# E-19_WIFI_BT_802_15_4.net
KiCad netlist of a schematic drawn in Altium Designer
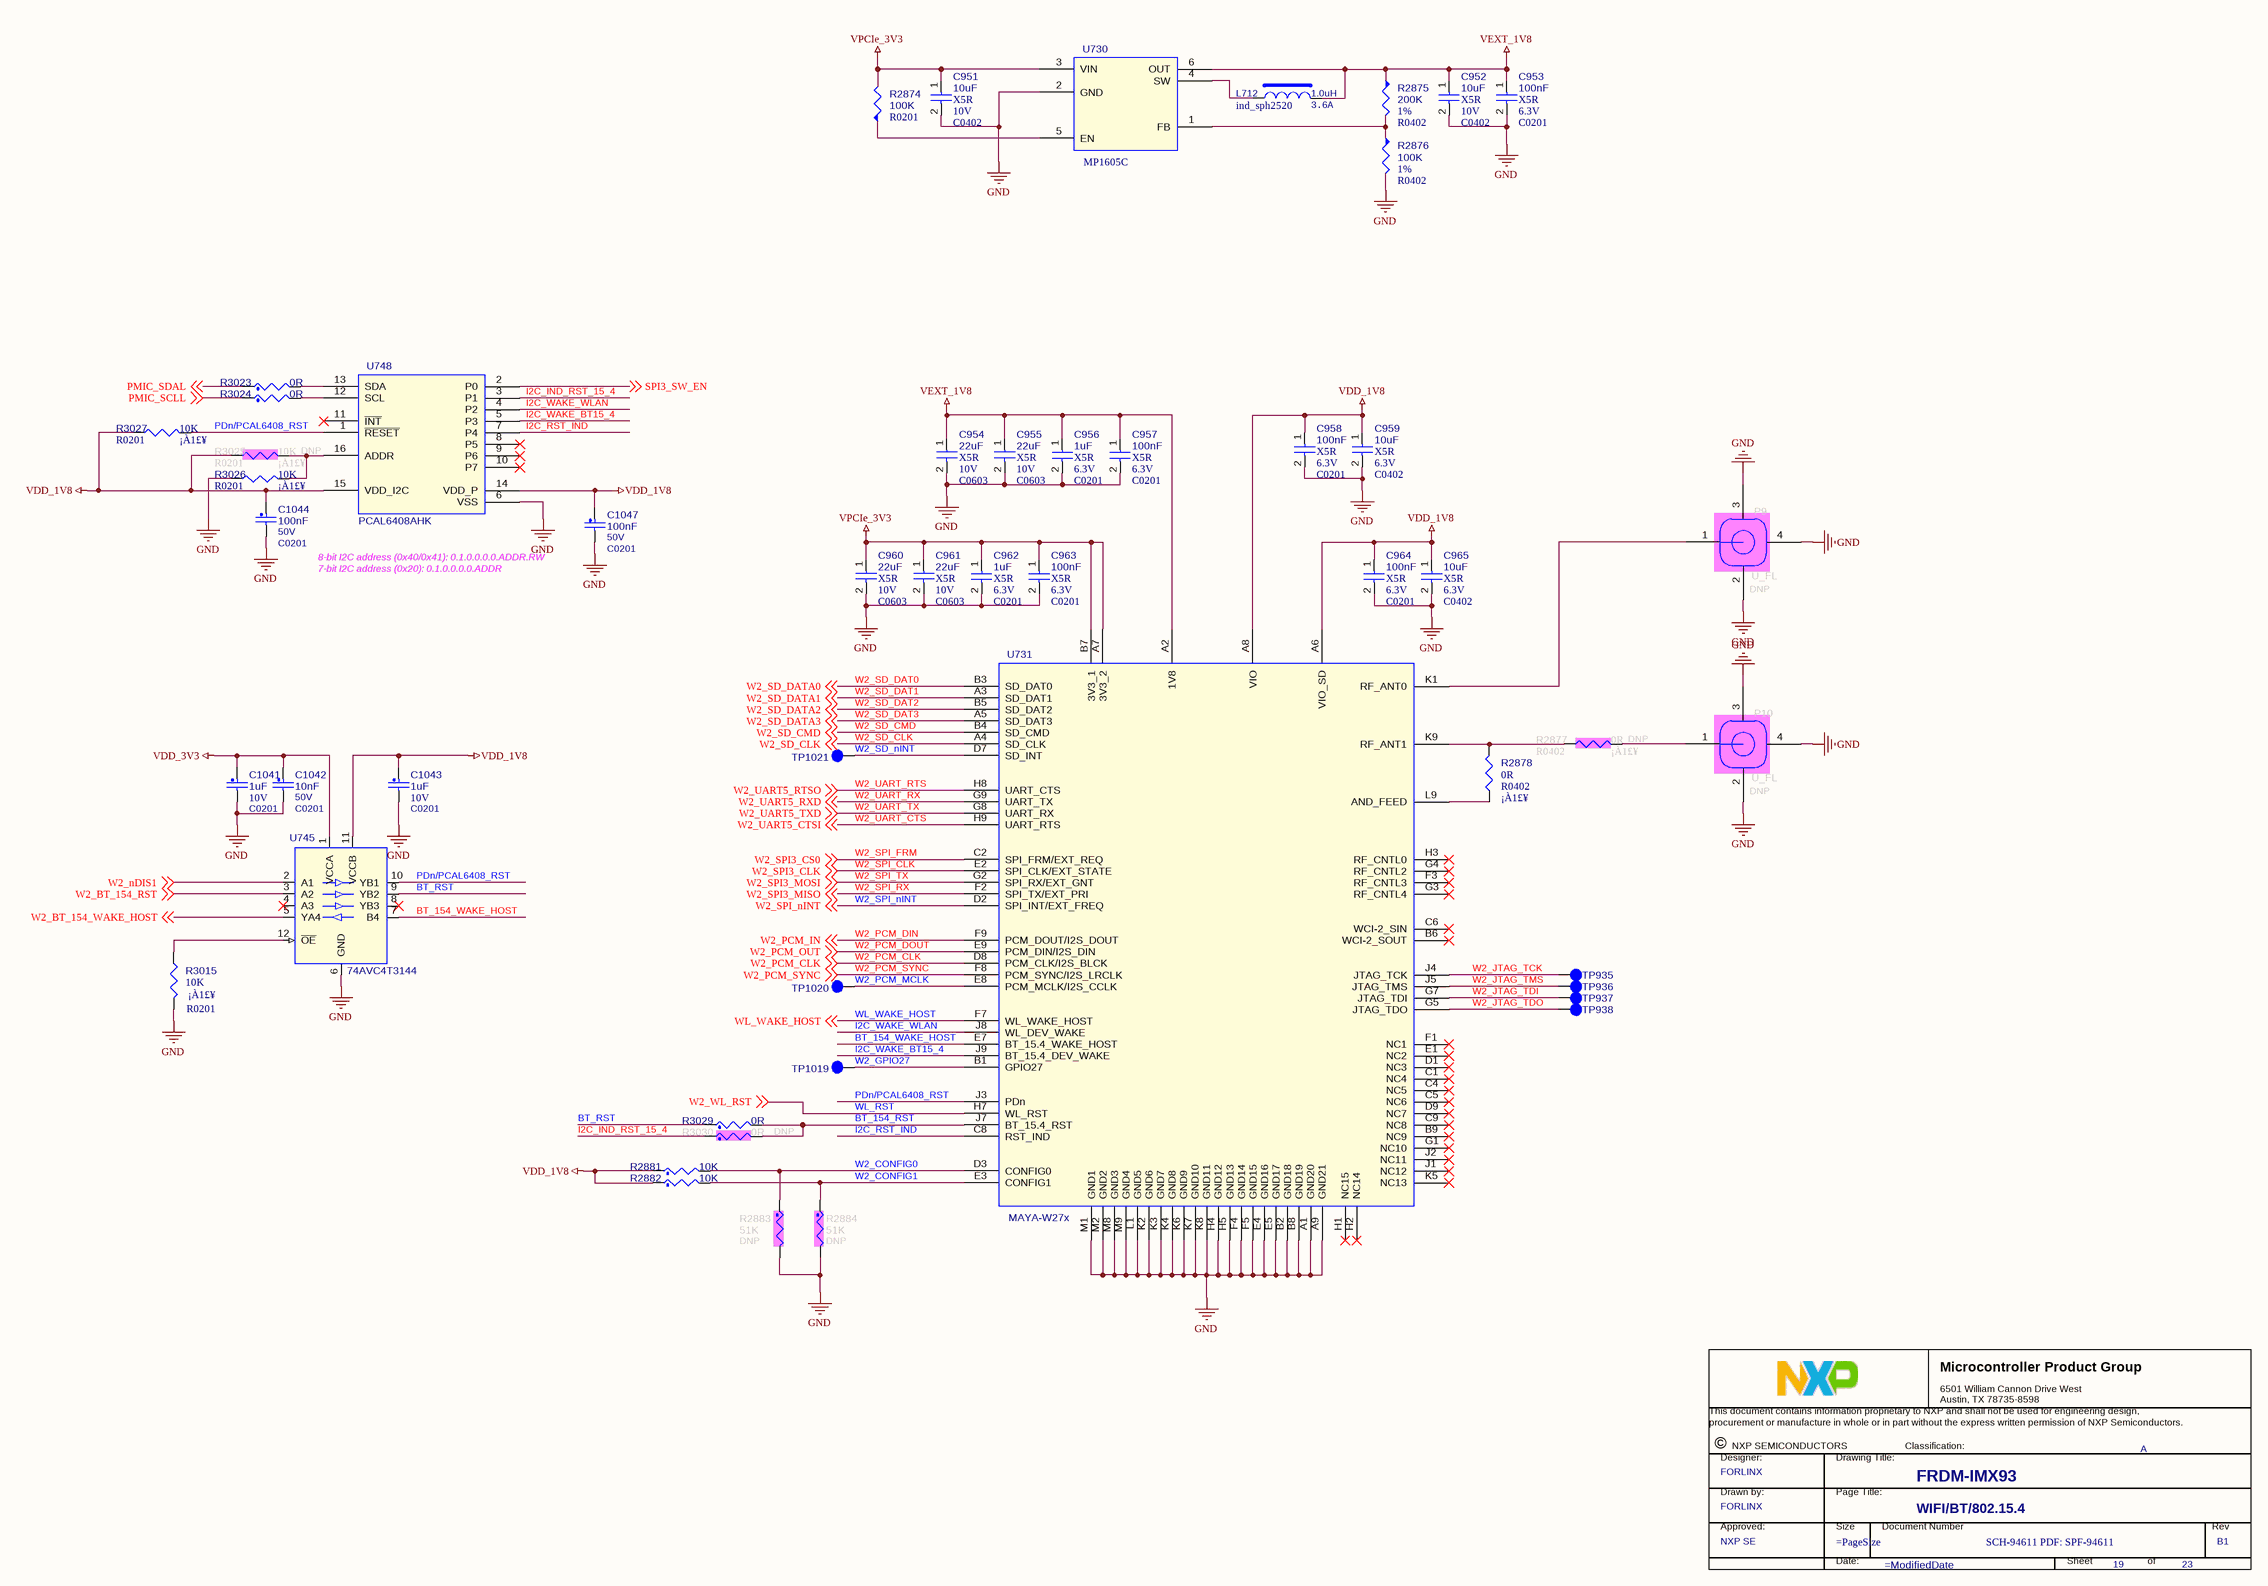
[diagram p0: E-19 WIFI_BT_802.15.4.SchDoc]

(export (version "E")
  (design (tool "Eeschema 10.0.6"))
  (components
    (comp (ref "C951")
      (value "10uF")
      (footprint "C0402")
      (description "0402,10uF,6.3V,+/-20%,X5R")
      (fields
        (field (name "VOLTAGE") "10V")
        (field (name "PCB FOOTPRINT") "C0402")
        (field (name "DIELECTRIC") "X5R")
        (field (name "MANUFACTURER") "murata")
        (field (name "TOLERANCE") "±20%")
        (field (name "CREATED BY") "JJJ")
      )
      (libsource (lib "*") (part "CAP NP"))
    )
    (comp (ref "C952")
      (value "10uF")
      (footprint "C0402")
      (description "0402,10uF,6.3V,+/-20%,X5R")
      (fields
        (field (name "VOLTAGE") "10V")
        (field (name "PCB FOOTPRINT") "C0402")
        (field (name "DIELECTRIC") "X5R")
        (field (name "MANUFACTURER") "murata")
        (field (name "TOLERANCE") "±20%")
        (field (name "CREATED BY") "JJJ")
      )
      (libsource (lib "*") (part "CAP NP"))
    )
    (comp (ref "C953")
      (value "100nF")
      (footprint "C0201")
      (description "0201,100nF,25V,+/-10%,X5R")
      (fields
        (field (name "VOLTAGE") "6.3V")
        (field (name "PCB FOOTPRINT") "C0201")
        (field (name "DIELECTRIC") "X5R")
        (field (name "TOLERANCE") "±10%")
        (field (name "MANUFACTURER") "FH(风华)")
        (field (name "CREATED BY") "JJJ")
      )
      (libsource (lib "*") (part "CAP NP"))
    )
    (comp (ref "C954")
      (value "22uF")
      (footprint "C0603")
      (description "0603,22uF,6.3V,+/-20%,X5R")
      (fields
        (field (name "VOLTAGE") "10V")
        (field (name "PCB FOOTPRINT") "C0603")
        (field (name "DIELECTRIC") "X5R")
        (field (name "MANUFACTURER") "TDK")
        (field (name "TOLERANCE") "10%")
        (field (name "CREATED BY") "JJJ")
      )
      (libsource (lib "*") (part "CAP NP"))
    )
    (comp (ref "C955")
      (value "22uF")
      (footprint "C0603")
      (description "0603,22uF,6.3V,+/-20%,X5R")
      (fields
        (field (name "VOLTAGE") "10V")
        (field (name "PCB FOOTPRINT") "C0603")
        (field (name "DIELECTRIC") "X5R")
        (field (name "MANUFACTURER") "TDK")
        (field (name "TOLERANCE") "10%")
        (field (name "CREATED BY") "JJJ")
      )
      (libsource (lib "*") (part "CAP NP"))
    )
    (comp (ref "C956")
      (value "1uF")
      (footprint "C0201")
      (description "0201,1uF,10V,+/-20%,X5R")
      (fields
        (field (name "VOLTAGE") "6.3V")
        (field (name "PCB FOOTPRINT") "C0201")
        (field (name "DIELECTRIC") "X5R")
        (field (name "MANUFACTURER") "FH(风华)")
        (field (name "TOLERANCE") "±10%")
        (field (name "CREATED BY") "JJJ")
      )
      (libsource (lib "*") (part "CAP NP"))
    )
    (comp (ref "C957")
      (value "100nF")
      (footprint "C0201")
      (description "0201,100nF,25V,+/-10%,X5R")
      (fields
        (field (name "VOLTAGE") "6.3V")
        (field (name "PCB FOOTPRINT") "C0201")
        (field (name "DIELECTRIC") "X5R")
        (field (name "TOLERANCE") "±10%")
        (field (name "MANUFACTURER") "FH(风华)")
        (field (name "CREATED BY") "JJJ")
      )
      (libsource (lib "*") (part "CAP NP"))
    )
    (comp (ref "C958")
      (value "100nF")
      (footprint "C0201")
      (description "0201,100nF,25V,+/-10%,X5R")
      (fields
        (field (name "VOLTAGE") "6.3V")
        (field (name "PCB FOOTPRINT") "C0201")
        (field (name "DIELECTRIC") "X5R")
        (field (name "MANUFACTURER") "FH(风华)")
        (field (name "TOLERANCE") "±10%")
        (field (name "CREATED BY") "JJJ")
      )
      (libsource (lib "*") (part "CAP NP"))
    )
    (comp (ref "C959")
      (value "10uF")
      (footprint "C0402")
      (description "0402,10uF,6.3V,+/-20%,X5R")
      (fields
        (field (name "VOLTAGE") "6.3V")
        (field (name "PCB FOOTPRINT") "C0402")
        (field (name "DIELECTRIC") "X5R")
        (field (name "MANUFACTURER") "FH(风华)")
        (field (name "TOLERANCE") "±10%")
        (field (name "CREATED BY") "JJJ")
      )
      (libsource (lib "*") (part "CAP NP"))
    )
    (comp (ref "C960")
      (value "22uF")
      (footprint "C0603")
      (description "0603,22uF,6.3V,+/-20%,X5R")
      (fields
        (field (name "VOLTAGE") "10V")
        (field (name "PCB FOOTPRINT") "C0603")
        (field (name "DIELECTRIC") "X5R")
        (field (name "MANUFACTURER") "TDK")
        (field (name "TOLERANCE") "10%")
        (field (name "CREATED BY") "JJJ")
      )
      (libsource (lib "*") (part "CAP NP"))
    )
    (comp (ref "C961")
      (value "22uF")
      (footprint "C0603")
      (description "0603,22uF,6.3V,+/-20%,X5R")
      (fields
        (field (name "VOLTAGE") "10V")
        (field (name "PCB FOOTPRINT") "C0603")
        (field (name "DIELECTRIC") "X5R")
        (field (name "MANUFACTURER") "TDK")
        (field (name "TOLERANCE") "10%")
        (field (name "CREATED BY") "JJJ")
      )
      (libsource (lib "*") (part "CAP NP"))
    )
    (comp (ref "C962")
      (value "1uF")
      (footprint "C0201")
      (description "0201,1uF,10V,+/-20%,X5R")
      (fields
        (field (name "VOLTAGE") "6.3V")
        (field (name "PCB FOOTPRINT") "C0201")
        (field (name "DIELECTRIC") "X5R")
        (field (name "TOLERANCE") "±10%")
        (field (name "MANUFACTURER") "FH(风华)")
        (field (name "CREATED BY") "JJJ")
      )
      (libsource (lib "*") (part "CAP NP"))
    )
    (comp (ref "C963")
      (value "100nF")
      (footprint "C0201")
      (description "0201,100nF,25V,+/-10%,X5R")
      (fields
        (field (name "VOLTAGE") "6.3V")
        (field (name "PCB FOOTPRINT") "C0201")
        (field (name "DIELECTRIC") "X5R")
        (field (name "TOLERANCE") "±10%")
        (field (name "MANUFACTURER") "FH(风华)")
        (field (name "CREATED BY") "JJJ")
      )
      (libsource (lib "*") (part "CAP NP"))
    )
    (comp (ref "C964")
      (value "100nF")
      (footprint "C0201")
      (description "0201,100nF,25V,+/-10%,X5R")
      (fields
        (field (name "VOLTAGE") "6.3V")
        (field (name "PCB FOOTPRINT") "C0201")
        (field (name "DIELECTRIC") "X5R")
        (field (name "MANUFACTURER") "FH(风华)")
        (field (name "TOLERANCE") "±10%")
        (field (name "CREATED BY") "JJJ")
      )
      (libsource (lib "*") (part "CAP NP"))
    )
    (comp (ref "C965")
      (value "10uF")
      (footprint "C0402")
      (description "0402,10uF,6.3V,+/-20%,X5R")
      (fields
        (field (name "VOLTAGE") "6.3V")
        (field (name "PCB FOOTPRINT") "C0402")
        (field (name "DIELECTRIC") "X5R")
        (field (name "MANUFACTURER") "FH(风华)")
        (field (name "TOLERANCE") "±10%")
        (field (name "CREATED BY") "JJJ")
      )
      (libsource (lib "*") (part "CAP NP"))
    )
    (comp (ref "C1041")
      (value "1uF")
      (footprint "C0201")
      (description "0201,1uF,10V,+/-20%,X5R")
      (fields
        (field (name "PCB FOOTPRINT") "C0201")
        (field (name "VOLTAGE") "10V")
        (field (name "TOLERANCE") "10%")
      )
      (libsource (lib "*") (part "CAP_NP"))
    )
    (comp (ref "C1042")
      (value "10nF")
      (footprint "C0201")
      (description "0201,10nF,25V,+/-10%,X7R")
      (fields
        (field (name "PCB FOOTPRINT") "C0201")
        (field (name "VOLTAGE") "50V")
        (field (name "TOLERANCE") "10%")
      )
      (libsource (lib "*") (part "CAP_NP"))
    )
    (comp (ref "C1043")
      (value "1uF")
      (footprint "C0201")
      (description "0201,1uF,10V,+/-20%,X5R")
      (fields
        (field (name "PCB FOOTPRINT") "C0201")
        (field (name "VOLTAGE") "10V")
        (field (name "TOLERANCE") "10%")
      )
      (libsource (lib "*") (part "CAP_NP"))
    )
    (comp (ref "C1044")
      (value "100nF")
      (footprint "C0201")
      (description "0201,100nF,25V,+/-10%,X5R")
      (fields
        (field (name "PCB FOOTPRINT") "C0201")
        (field (name "TOLERANCE") "10%")
        (field (name "VOLTAGE") "50V")
      )
      (libsource (lib "*") (part "CAP_NP"))
    )
    (comp (ref "C1047")
      (value "100nF")
      (footprint "C0201")
      (description "0201,100nF,25V,+/-10%,X5R")
      (fields
        (field (name "PCB FOOTPRINT") "C0201")
        (field (name "VOLTAGE") "50V")
        (field (name "TOLERANCE") "10%")
      )
      (libsource (lib "*") (part "CAP_NP"))
    )
    (comp (ref "L712")
      (value "1.0uH")
      (footprint "ind_sph2520")
      (description "1uH ,2.5*2.0*1.2mm, 3.6A")
      (fields
        (field (name "ISAT") "3.6A")
        (field (name "PCB FOOTPRINT") "ind_sph2520")
        (field (name "TOLERANCE") "20%")
        (field (name "MANUFACTURER") "TDK")
        (field (name "CREATED BY") "JJJ")
      )
      (libsource (lib "*") (part "INDUCTORS OF FERRITE"))
    )
    (comp (ref "P9")
      (value "U_FL")
      (footprint "IPEX_4")
      (description "IPEX transposon, 4th generation")
      (fields (field (name "ASSY_OPT") "DNP"))
      (libsource (lib "*") (part "U_FL"))
    )
    (comp (ref "P10")
      (value "U_FL")
      (footprint "IPEX_4")
      (description "IPEX transposon, 4th generation")
      (fields (field (name "ASSY_OPT") "DNP"))
      (libsource (lib "*") (part "U_FL"))
    )
    (comp (ref "R2874")
      (value "100K")
      (footprint "R0201")
      (description "0201,100K,+/-1%")
      (fields
        (field (name "TOLERANCE") "5%")
        (field (name "PCB FOOTPRINT") "R0201")
        (field (name "MANUFACTURER") "YAGEO")
        (field (name "CREATED BY") "YTL")
      )
      (libsource (lib "*") (part "RESISTOR5"))
    )
    (comp (ref "R2875")
      (value "200K")
      (footprint "R0402")
      (description "0402,200K,+/-1%")
      (fields
        (field (name "PCB FOOTPRINT") "R0402")
        (field (name "TOLERANCE") "1%")
        (field (name "MANUFACTURER") "YAGEO")
        (field (name "CREATED BY") "YTL")
      )
      (libsource (lib "*") (part "RESISTOR1"))
    )
    (comp (ref "R2876")
      (value "100K")
      (footprint "R0402")
      (description "0402,100K,+/-1%")
      (fields
        (field (name "PCB FOOTPRINT") "R0402")
        (field (name "TOLERANCE") "1%")
        (field (name "MANUFACTURER") "YAGEO")
        (field (name "CREATED BY") "YTL")
      )
      (libsource (lib "*") (part "RESISTOR1"))
    )
    (comp (ref "R2877")
      (value "0R")
      (footprint "R0402")
      (description "0402,0Ohm,+/-1%")
      (fields
        (field (name "PCB FOOTPRINT") "R0402")
        (field (name "PRECISION") "±1％")
        (field (name "ASSY_OPT") "DNP")
      )
      (libsource (lib "*") (part "R0402,4.7K"))
    )
    (comp (ref "R2878")
      (value "0R")
      (footprint "R0402")
      (description "0402,0Ohm,+/-1%")
      (fields (field (name "PCB FOOTPRINT") "R0402") (field (name "PRECISION") "±1％"))
      (libsource (lib "*") (part "R0402,4.7K"))
    )
    (comp (ref "R2881")
      (value "10K")
      (footprint "R0201")
      (description "0201,10K,+/-5%")
      (fields (field (name "TOLERANCE") "5%") (field (name "VOLTAGE") "1/16W"))
      (libsource (lib "*") (part "RES"))
    )
    (comp (ref "R2882")
      (value "10K")
      (footprint "R0201")
      (description "0201,10K,+/-5%")
      (fields (field (name "TOLERANCE") "5%") (field (name "VOLTAGE") "1/16W"))
      (libsource (lib "*") (part "RES"))
    )
    (comp (ref "R2883")
      (value "51K")
      (footprint "R0201")
      (description "0201,51K,+/-1%,RC-01W5102FT")
      (fields
        (field (name "ASSY_OPT") "DNP")
        (field (name "TOLERANCE") "5%")
        (field (name "VOLTAGE") "1/16W")
      )
      (libsource (lib "*") (part "RES"))
    )
    (comp (ref "R2884")
      (value "51K")
      (footprint "R0201")
      (description "0201,51K,+/-1%,RC-01W5102FT")
      (fields
        (field (name "ASSY_OPT") "DNP")
        (field (name "VOLTAGE") "1/16W")
        (field (name "TOLERANCE") "5%")
      )
      (libsource (lib "*") (part "RES"))
    )
    (comp (ref "R3015")
      (value "10K")
      (footprint "R0201")
      (description "0201,10K,+/-5%")
      (fields (field (name "PRECISION") "±1％") (field (name "PCB FOOTPRINT") "R0201"))
      (libsource (lib "*") (part "R0402,10K"))
    )
    (comp (ref "R3023")
      (value "0R")
      (footprint "R0201")
      (description "0201,0Ohm,+/-5%")
      (fields (field (name "TOLERANCE") "5%") (field (name "VOLTAGE") "1/16W"))
      (libsource (lib "*") (part "RES"))
    )
    (comp (ref "R3024")
      (value "0R")
      (footprint "R0201")
      (description "0201,0Ohm,+/-5%")
      (fields (field (name "TOLERANCE") "5%") (field (name "VOLTAGE") "1/16W"))
      (libsource (lib "*") (part "RES"))
    )
    (comp (ref "R3025")
      (value "10K")
      (footprint "R0201")
      (description "0201,10K,+/-5%")
      (fields
        (field (name "PRECISION") "±1％")
        (field (name "PCB FOOTPRINT") "R0201")
        (field (name "ASSY_OPT") "DNP")
      )
      (libsource (lib "*") (part "R0402,10K"))
    )
    (comp (ref "R3026")
      (value "10K")
      (footprint "R0201")
      (description "0201,10K,+/-5%")
      (fields (field (name "PRECISION") "±1％") (field (name "PCB FOOTPRINT") "R0201"))
      (libsource (lib "*") (part "R0402,10K"))
    )
    (comp (ref "R3027")
      (value "10K")
      (footprint "R0201")
      (description "0201,10K,+/-5%")
      (fields (field (name "PRECISION") "±1％") (field (name "PCB FOOTPRINT") "R0201"))
      (libsource (lib "*") (part "R0402,10K"))
    )
    (comp (ref "R3029")
      (value "0R")
      (footprint "R0201")
      (description "0201,0Ohm,+/-5%")
      (fields (field (name "TOLERANCE") "5%") (field (name "VOLTAGE") "1/16W"))
      (libsource (lib "*") (part "RES"))
    )
    (comp (ref "R3030")
      (value "0R")
      (footprint "R0201")
      (description "0201,0Ohm,+/-5%")
      (fields
        (field (name "ASSY_OPT") "DNP")
        (field (name "TOLERANCE") "5%")
        (field (name "VOLTAGE") "1/16W")
      )
      (libsource (lib "*") (part "RES"))
    )
    (comp (ref "TP935")
      (value "TPAD_015")
      (footprint "tpad_015")
      (description "no part to order")
      (libsource (lib "*") (part "TESTLOOP"))
    )
    (comp (ref "TP936")
      (value "TPAD_015")
      (footprint "tpad_015")
      (description "no part to order")
      (libsource (lib "*") (part "TESTLOOP"))
    )
    (comp (ref "TP937")
      (value "TPAD_015")
      (footprint "tpad_015")
      (description "no part to order")
      (libsource (lib "*") (part "TESTLOOP"))
    )
    (comp (ref "TP938")
      (value "TPAD_015")
      (footprint "tpad_015")
      (description "no part to order")
      (libsource (lib "*") (part "TESTLOOP"))
    )
    (comp (ref "TP1019")
      (value "TPAD_015")
      (footprint "tpad_015")
      (description "no part to order")
      (libsource (lib "*") (part "TESTLOOP"))
    )
    (comp (ref "TP1020")
      (value "TPAD_015")
      (footprint "tpad_015")
      (description "no part to order")
      (libsource (lib "*") (part "TESTLOOP"))
    )
    (comp (ref "TP1021")
      (value "TPAD_015")
      (footprint "tpad_015")
      (description "no part to order")
      (libsource (lib "*") (part "TESTLOOP"))
    )
    (comp (ref "U730")
      (value "MP1605C")
      (footprint "SOT563")
      (description "MP1605GTF,SOT563")
      (libsource (lib "*") (part "MP1605C"))
    )
    (comp (ref "U731")
      (value "MAYA-W27x")
      (footprint "MAYA-W2")
      (description "MAYA-W276,LGA86,10.4*14.3*2.0mm,0-70+C(SDIO,UART,SPI)")
      (libsource (lib "*") (part "MAYA-W27x"))
    )
    (comp (ref "U745")
      (value "74AVC4T3144")
      (footprint "uqfn12_1p7x2mm")
      (description "74AVC4T3144GU12,XQFN12,1.70*2.0,4-bit dual-supply buffer/level translator;3-state")
      (fields (field (name "VOLTAGE") "0.9-3.6V"))
      (libsource (lib "*") (part "TXB0304RUT_12P_B_0"))
    )
    (comp (ref "U748")
      (value "PCAL6408AHK")
      (footprint "XQFN16")
      (description "PCAL6408AHK,XQFN16,-40~85+C,I2C Extended 8-bit GPIO")
      (libsource (lib "*") (part "PCAL6408AHK"))
    )
  )
  (nets
    (net (code "1") (name "/BT_154_RST") (class "Default")
      (node (ref "R3029") (pin "2") (pinfunction "2_2") (pintype "passive"))
      (node (ref "R3030") (pin "2") (pinfunction "2_2") (pintype "passive"))
      (node (ref "U731") (pin "J7") (pinfunction "BT_15.4_RST_J7") (pintype "passive"))
    )
    (net (code "2") (name "/BT_154_WAKE_HOST") (class "Default")
      (node (ref "U731") (pin "E7") (pinfunction "BT_15.4_WAKE_HOST_E7") (pintype "passive"))
      (node (ref "U745") (pin "7") (pinfunction "B4_7") (pintype "bidirectional"))
    )
    (net (code "3") (name "/BT_RST") (class "Default")
      (node (ref "R3029") (pin "1") (pinfunction "1_1") (pintype "passive"))
      (node (ref "U745") (pin "9") (pinfunction "YB2_9") (pintype "bidirectional"))
    )
    (net (code "4") (name "/I2C_IND_RST_15_4") (class "Default")
      (node (ref "R3030") (pin "1") (pinfunction "1_1") (pintype "passive"))
      (node (ref "U748") (pin "3") (pinfunction "P1_3") (pintype "passive"))
    )
    (net (code "5") (name "/I2C_RST_IND") (class "Default")
      (node (ref "U731") (pin "C8") (pinfunction "RST_IND_C8") (pintype "passive"))
      (node (ref "U748") (pin "7") (pinfunction "P4_7") (pintype "passive"))
    )
    (net (code "6") (name "/I2C_WAKE_BT15_4") (class "Default")
      (node (ref "U731") (pin "J9") (pinfunction "BT_15.4_DEV_WAKE_J9") (pintype "passive"))
      (node (ref "U748") (pin "5") (pinfunction "P3_5") (pintype "passive"))
    )
    (net (code "7") (name "/I2C_WAKE_WLAN") (class "Default")
      (node (ref "U731") (pin "J8") (pinfunction "WL_DEV_WAKE_J8") (pintype "passive"))
      (node (ref "U748") (pin "4") (pinfunction "P2_4") (pintype "passive"))
    )
    (net (code "8") (name "/PDn{slash}PCAL6408_RST") (class "Default")
      (node (ref "R3027") (pin "2") (pinfunction "2_2") (pintype "passive"))
      (node (ref "U731") (pin "J3") (pinfunction "PDn_J3") (pintype "passive"))
      (node (ref "U745") (pin "10") (pinfunction "YB1_10") (pintype "bidirectional"))
      (node (ref "U748") (pin "1") (pinfunction "~{RESET}_1") (pintype "passive"))
    )
    (net (code "9") (name "/W2_CONFIG0") (class "Default")
      (node (ref "R2881") (pin "2") (pinfunction "2_2") (pintype "passive"))
      (node (ref "R2883") (pin "1") (pinfunction "1_1") (pintype "passive"))
      (node (ref "U731") (pin "D3") (pinfunction "CONFIG0_D3") (pintype "passive"))
    )
    (net (code "10") (name "/W2_CONFIG1") (class "Default")
      (node (ref "R2882") (pin "2") (pinfunction "2_2") (pintype "passive"))
      (node (ref "R2884") (pin "1") (pinfunction "1_1") (pintype "passive"))
      (node (ref "U731") (pin "E3") (pinfunction "CONFIG1_E3") (pintype "passive"))
    )
    (net (code "11") (name "/W2_GPIO27") (class "Default")
      (node (ref "TP1019") (pin "1") (pinfunction "Pin1_1") (pintype "passive"))
      (node (ref "U731") (pin "B1") (pinfunction "GPIO27_B1") (pintype "passive"))
    )
    (net (code "12") (name "/W2_JTAG_TCK") (class "Default")
      (node (ref "TP935") (pin "1") (pinfunction "Pin1_1") (pintype "passive"))
      (node (ref "U731") (pin "J4") (pinfunction "JTAG_TCK_J4") (pintype "passive"))
    )
    (net (code "13") (name "/W2_JTAG_TDI") (class "Default")
      (node (ref "TP937") (pin "1") (pinfunction "Pin1_1") (pintype "passive"))
      (node (ref "U731") (pin "G7") (pinfunction "JTAG_TDI_G7") (pintype "passive"))
    )
    (net (code "14") (name "/W2_JTAG_TDO") (class "Default")
      (node (ref "TP938") (pin "1") (pinfunction "Pin1_1") (pintype "passive"))
      (node (ref "U731") (pin "G5") (pinfunction "JTAG_TDO_G5") (pintype "passive"))
    )
    (net (code "15") (name "/W2_JTAG_TMS") (class "Default")
      (node (ref "TP936") (pin "1") (pinfunction "Pin1_1") (pintype "passive"))
      (node (ref "U731") (pin "J5") (pinfunction "JTAG_TMS_J5") (pintype "passive"))
    )
    (net (code "16") (name "/W2_PCM_MCLK") (class "Default")
      (node (ref "TP1020") (pin "1") (pinfunction "Pin1_1") (pintype "passive"))
      (node (ref "U731") (pin "E8") (pinfunction "PCM_MCLK/I2S_CCLK_E8") (pintype "passive"))
    )
    (net (code "17") (name "/W2_SD_nINT") (class "Default")
      (node (ref "TP1021") (pin "1") (pinfunction "Pin1_1") (pintype "passive"))
      (node (ref "U731") (pin "D7") (pinfunction "SD_INT_D7") (pintype "passive"))
    )
    (net (code "18") (name "GND") (class "Default")
      (node (ref "C1041") (pin "2") (pinfunction "2_2") (pintype "passive"))
      (node (ref "C1042") (pin "2") (pinfunction "2_2") (pintype "passive"))
      (node (ref "C1043") (pin "2") (pinfunction "2_2") (pintype "passive"))
      (node (ref "C1044") (pin "2") (pinfunction "2_2") (pintype "passive"))
      (node (ref "C1047") (pin "2") (pinfunction "2_2") (pintype "passive"))
      (node (ref "C951") (pin "2") (pinfunction "2_2") (pintype "passive"))
      (node (ref "C952") (pin "2") (pinfunction "2_2") (pintype "passive"))
      (node (ref "C953") (pin "2") (pinfunction "2_2") (pintype "passive"))
      (node (ref "C954") (pin "2") (pinfunction "2_2") (pintype "passive"))
      (node (ref "C955") (pin "2") (pinfunction "2_2") (pintype "passive"))
      (node (ref "C956") (pin "2") (pinfunction "2_2") (pintype "passive"))
      (node (ref "C957") (pin "2") (pinfunction "2_2") (pintype "passive"))
      (node (ref "C958") (pin "2") (pinfunction "2_2") (pintype "passive"))
      (node (ref "C959") (pin "2") (pinfunction "2_2") (pintype "passive"))
      (node (ref "C960") (pin "2") (pinfunction "2_2") (pintype "passive"))
      (node (ref "C961") (pin "2") (pinfunction "2_2") (pintype "passive"))
      (node (ref "C962") (pin "2") (pinfunction "2_2") (pintype "passive"))
      (node (ref "C963") (pin "2") (pinfunction "2_2") (pintype "passive"))
      (node (ref "C964") (pin "2") (pinfunction "2_2") (pintype "passive"))
      (node (ref "C965") (pin "2") (pinfunction "2_2") (pintype "passive"))
      (node (ref "P10") (pin "2") (pinfunction "2_2") (pintype "passive"))
      (node (ref "P10") (pin "3") (pinfunction "3_3") (pintype "passive"))
      (node (ref "P10") (pin "4") (pinfunction "4_4") (pintype "passive"))
      (node (ref "P9") (pin "2") (pinfunction "2_2") (pintype "passive"))
      (node (ref "P9") (pin "3") (pinfunction "3_3") (pintype "passive"))
      (node (ref "P9") (pin "4") (pinfunction "4_4") (pintype "passive"))
      (node (ref "R2876") (pin "2") (pinfunction "2_2") (pintype "passive"))
      (node (ref "R2883") (pin "2") (pinfunction "2_2") (pintype "passive"))
      (node (ref "R2884") (pin "2") (pinfunction "2_2") (pintype "passive"))
      (node (ref "R3015") (pin "2") (pinfunction "2_2") (pintype "passive"))
      (node (ref "R3026") (pin "1") (pinfunction "1_1") (pintype "passive"))
      (node (ref "U730") (pin "2") (pinfunction "GND_2") (pintype "passive"))
      (node (ref "U731") (pin "A1") (pinfunction "GND20_A1") (pintype "passive"))
      (node (ref "U731") (pin "A9") (pinfunction "GND21_A9") (pintype "passive"))
      (node (ref "U731") (pin "B2") (pinfunction "GND18_B2") (pintype "passive"))
      (node (ref "U731") (pin "B8") (pinfunction "GND19_B8") (pintype "passive"))
      (node (ref "U731") (pin "E4") (pinfunction "GND16_E4") (pintype "passive"))
      (node (ref "U731") (pin "E5") (pinfunction "GND17_E5") (pintype "passive"))
      (node (ref "U731") (pin "F4") (pinfunction "GND14_F4") (pintype "passive"))
      (node (ref "U731") (pin "F5") (pinfunction "GND15_F5") (pintype "passive"))
      (node (ref "U731") (pin "H4") (pinfunction "GND12_H4") (pintype "passive"))
      (node (ref "U731") (pin "H5") (pinfunction "GND13_H5") (pintype "passive"))
      (node (ref "U731") (pin "K2") (pinfunction "GND6_K2") (pintype "passive"))
      (node (ref "U731") (pin "K3") (pinfunction "GND7_K3") (pintype "passive"))
      (node (ref "U731") (pin "K4") (pinfunction "GND8_K4") (pintype "passive"))
      (node (ref "U731") (pin "K6") (pinfunction "GND9_K6") (pintype "passive"))
      (node (ref "U731") (pin "K7") (pinfunction "GND10_K7") (pintype "passive"))
      (node (ref "U731") (pin "K8") (pinfunction "GND11_K8") (pintype "passive"))
      (node (ref "U731") (pin "L1") (pinfunction "GND5_L1") (pintype "passive"))
      (node (ref "U731") (pin "M1") (pinfunction "GND1_M1") (pintype "passive"))
      (node (ref "U731") (pin "M2") (pinfunction "GND2_M2") (pintype "passive"))
      (node (ref "U731") (pin "M8") (pinfunction "GND3_M8") (pintype "passive"))
      (node (ref "U731") (pin "M9") (pinfunction "GND4_M9") (pintype "passive"))
      (node (ref "U745") (pin "6") (pinfunction "GND_6") (pintype "power_in"))
      (node (ref "U748") (pin "6") (pinfunction "VSS_6") (pintype "passive"))
    )
    (net (code "19") (name "Net-(P10-Pad1)") (class "Default")
      (node (ref "P10") (pin "1") (pinfunction "1_1") (pintype "passive"))
      (node (ref "R2877") (pin "2") (pinfunction "2_2") (pintype "passive"))
    )
    (net (code "20") (name "Net-(U730-EN)") (class "Default")
      (node (ref "R2874") (pin "1") (pinfunction "1_1") (pintype "passive"))
      (node (ref "U730") (pin "5") (pinfunction "EN_5") (pintype "passive"))
    )
    (net (code "21") (name "Net-(U730-FB)") (class "Default")
      (node (ref "R2875") (pin "2") (pinfunction "2_2") (pintype "passive"))
      (node (ref "R2876") (pin "1") (pinfunction "1_1") (pintype "passive"))
      (node (ref "U730") (pin "1") (pinfunction "FB_1") (pintype "passive"))
    )
    (net (code "22") (name "Net-(U730-SW)") (class "Default")
      (node (ref "L712") (pin "1") (pinfunction "1_1") (pintype "passive"))
      (node (ref "U730") (pin "4") (pinfunction "SW_4") (pintype "passive"))
    )
    (net (code "23") (name "Net-(U731-AND_FEED)") (class "Default")
      (node (ref "R2878") (pin "1") (pinfunction "1_1") (pintype "passive"))
      (node (ref "U731") (pin "L9") (pinfunction "AND_FEED_L9") (pintype "passive"))
    )
    (net (code "24") (name "Net-(U731-RF_ANT0)") (class "Default")
      (node (ref "P9") (pin "1") (pinfunction "1_1") (pintype "passive"))
      (node (ref "U731") (pin "K1") (pinfunction "RF_ANT0_K1") (pintype "passive"))
    )
    (net (code "25") (name "Net-(U731-RF_ANT1)") (class "Default")
      (node (ref "R2877") (pin "1") (pinfunction "1_1") (pintype "passive"))
      (node (ref "R2878") (pin "2") (pinfunction "2_2") (pintype "passive"))
      (node (ref "U731") (pin "K9") (pinfunction "RF_ANT1_K9") (pintype "passive"))
    )
    (net (code "26") (name "Net-(U745-~{OE})") (class "Default")
      (node (ref "R3015") (pin "1") (pinfunction "1_1") (pintype "passive"))
      (node (ref "U745") (pin "12") (pinfunction "~{OE}_12") (pintype "input"))
    )
    (net (code "27") (name "Net-(U748-ADDR)") (class "Default")
      (node (ref "R3025") (pin "2") (pinfunction "2_2") (pintype "passive"))
      (node (ref "R3026") (pin "2") (pinfunction "2_2") (pintype "passive"))
      (node (ref "U748") (pin "16") (pinfunction "ADDR_16") (pintype "passive"))
    )
    (net (code "28") (name "Net-(U748-SCL)") (class "Default")
      (node (ref "R3024") (pin "2") (pinfunction "2_2") (pintype "passive"))
      (node (ref "U748") (pin "12") (pinfunction "SCL_12") (pintype "passive"))
    )
    (net (code "29") (name "Net-(U748-SDA)") (class "Default")
      (node (ref "R3023") (pin "2") (pinfunction "2_2") (pintype "passive"))
      (node (ref "U748") (pin "13") (pinfunction "SDA_13") (pintype "passive"))
    )
    (net (code "30") (name "PMIC_SCLL") (class "Default")
      (node (ref "R3024") (pin "1") (pinfunction "1_1") (pintype "passive"))
    )
    (net (code "31") (name "PMIC_SDAL") (class "Default")
      (node (ref "R3023") (pin "1") (pinfunction "1_1") (pintype "passive"))
    )
    (net (code "32") (name "SPI3_SW_EN") (class "Default")
      (node (ref "U748") (pin "2") (pinfunction "P0_2") (pintype "passive"))
    )
    (net (code "33") (name "VDD_1V8") (class "Default")
      (node (ref "C1043") (pin "1") (pinfunction "1_1") (pintype "passive"))
      (node (ref "C1044") (pin "1") (pinfunction "1_1") (pintype "passive"))
      (node (ref "C1047") (pin "1") (pinfunction "1_1") (pintype "passive"))
      (node (ref "C958") (pin "1") (pinfunction "1_1") (pintype "passive"))
      (node (ref "C959") (pin "1") (pinfunction "1_1") (pintype "passive"))
      (node (ref "C964") (pin "1") (pinfunction "1_1") (pintype "passive"))
      (node (ref "C965") (pin "1") (pinfunction "1_1") (pintype "passive"))
      (node (ref "R2881") (pin "1") (pinfunction "1_1") (pintype "passive"))
      (node (ref "R2882") (pin "1") (pinfunction "1_1") (pintype "passive"))
      (node (ref "R3025") (pin "1") (pinfunction "1_1") (pintype "passive"))
      (node (ref "R3027") (pin "1") (pinfunction "1_1") (pintype "passive"))
      (node (ref "U731") (pin "A6") (pinfunction "VIO_SD_A6") (pintype "passive"))
      (node (ref "U731") (pin "A8") (pinfunction "VIO_A8") (pintype "passive"))
      (node (ref "U745") (pin "11") (pinfunction "VCCB_11") (pintype "power_in"))
      (node (ref "U748") (pin "14") (pinfunction "VDD_P_14") (pintype "passive"))
      (node (ref "U748") (pin "15") (pinfunction "VDD_I2C_15") (pintype "passive"))
    )
    (net (code "34") (name "VDD_3V3") (class "Default")
      (node (ref "C1041") (pin "1") (pinfunction "1_1") (pintype "passive"))
      (node (ref "C1042") (pin "1") (pinfunction "1_1") (pintype "passive"))
      (node (ref "U745") (pin "1") (pinfunction "VCCA_1") (pintype "power_in"))
    )
    (net (code "35") (name "VEXT_1V8") (class "Default")
      (node (ref "C952") (pin "1") (pinfunction "1_1") (pintype "passive"))
      (node (ref "C953") (pin "1") (pinfunction "1_1") (pintype "passive"))
      (node (ref "C954") (pin "1") (pinfunction "1_1") (pintype "passive"))
      (node (ref "C955") (pin "1") (pinfunction "1_1") (pintype "passive"))
      (node (ref "C956") (pin "1") (pinfunction "1_1") (pintype "passive"))
      (node (ref "C957") (pin "1") (pinfunction "1_1") (pintype "passive"))
      (node (ref "L712") (pin "2") (pinfunction "2_2") (pintype "passive"))
      (node (ref "R2875") (pin "1") (pinfunction "1_1") (pintype "passive"))
      (node (ref "U730") (pin "6") (pinfunction "OUT_6") (pintype "passive"))
      (node (ref "U731") (pin "A2") (pinfunction "1V8_A2") (pintype "passive"))
    )
    (net (code "36") (name "VPCIe_3V3") (class "Default")
      (node (ref "C951") (pin "1") (pinfunction "1_1") (pintype "passive"))
      (node (ref "C960") (pin "1") (pinfunction "1_1") (pintype "passive"))
      (node (ref "C961") (pin "1") (pinfunction "1_1") (pintype "passive"))
      (node (ref "C962") (pin "1") (pinfunction "1_1") (pintype "passive"))
      (node (ref "C963") (pin "1") (pinfunction "1_1") (pintype "passive"))
      (node (ref "R2874") (pin "2") (pinfunction "2_2") (pintype "passive"))
      (node (ref "U730") (pin "3") (pinfunction "VIN_3") (pintype "passive"))
      (node (ref "U731") (pin "A7") (pinfunction "3V3_2_A7") (pintype "passive"))
      (node (ref "U731") (pin "B7") (pinfunction "3V3_1_B7") (pintype "passive"))
    )
    (net (code "37") (name "W2_BT_154_RST") (class "Default")
      (node (ref "U745") (pin "3") (pinfunction "A2_3") (pintype "bidirectional"))
    )
    (net (code "38") (name "W2_BT_154_WAKE_HOST") (class "Default")
      (node (ref "U745") (pin "5") (pinfunction "YA4_5") (pintype "bidirectional"))
    )
    (net (code "39") (name "W2_PCM_CLK") (class "Default")
      (node (ref "U731") (pin "D8") (pinfunction "PCM_CLK/I2S_BLCK_D8") (pintype "passive"))
    )
    (net (code "40") (name "W2_PCM_IN") (class "Default")
      (node (ref "U731") (pin "F9") (pinfunction "PCM_DOUT/I2S_DOUT_F9") (pintype "passive"))
    )
    (net (code "41") (name "W2_PCM_OUT") (class "Default")
      (node (ref "U731") (pin "E9") (pinfunction "PCM_DIN/I2S_DIN_E9") (pintype "passive"))
    )
    (net (code "42") (name "W2_PCM_SYNC") (class "Default")
      (node (ref "U731") (pin "F8") (pinfunction "PCM_SYNC/I2S_LRCLK_F8") (pintype "passive"))
    )
    (net (code "43") (name "W2_SD_CLK") (class "Default")
      (node (ref "U731") (pin "A4") (pinfunction "SD_CLK_A4") (pintype "passive"))
    )
    (net (code "44") (name "W2_SD_CMD") (class "Default")
      (node (ref "U731") (pin "B4") (pinfunction "SD_CMD_B4") (pintype "passive"))
    )
    (net (code "45") (name "W2_SD_DATA0") (class "Default")
      (node (ref "U731") (pin "B3") (pinfunction "SD_DAT0_B3") (pintype "passive"))
    )
    (net (code "46") (name "W2_SD_DATA1") (class "Default")
      (node (ref "U731") (pin "A3") (pinfunction "SD_DAT1_A3") (pintype "passive"))
    )
    (net (code "47") (name "W2_SD_DATA2") (class "Default")
      (node (ref "U731") (pin "B5") (pinfunction "SD_DAT2_B5") (pintype "passive"))
    )
    (net (code "48") (name "W2_SD_DATA3") (class "Default")
      (node (ref "U731") (pin "A5") (pinfunction "SD_DAT3_A5") (pintype "passive"))
    )
    (net (code "49") (name "W2_SPI3_CLK") (class "Default")
      (node (ref "U731") (pin "E2") (pinfunction "SPI_CLK/EXT_STATE_E2") (pintype "passive"))
    )
    (net (code "50") (name "W2_SPI3_CS0") (class "Default")
      (node (ref "U731") (pin "C2") (pinfunction "SPI_FRM/EXT_REQ_C2") (pintype "passive"))
    )
    (net (code "51") (name "W2_SPI3_MISO") (class "Default")
      (node (ref "U731") (pin "F2") (pinfunction "SPI_TX/EXT_PRI_F2") (pintype "passive"))
    )
    (net (code "52") (name "W2_SPI3_MOSI") (class "Default")
      (node (ref "U731") (pin "G2") (pinfunction "SPI_RX/EXT_GNT_G2") (pintype "passive"))
    )
    (net (code "53") (name "W2_SPI_nINT") (class "Default")
      (node (ref "U731") (pin "D2") (pinfunction "SPI_INT/EXT_FREQ_D2") (pintype "passive"))
    )
    (net (code "54") (name "W2_UART5_CTSI") (class "Default")
      (node (ref "U731") (pin "H9") (pinfunction "UART_RTS_H9") (pintype "passive"))
    )
    (net (code "55") (name "W2_UART5_RTSO") (class "Default")
      (node (ref "U731") (pin "H8") (pinfunction "UART_CTS_H8") (pintype "passive"))
    )
    (net (code "56") (name "W2_UART5_RXD") (class "Default")
      (node (ref "U731") (pin "G9") (pinfunction "UART_TX_G9") (pintype "passive"))
    )
    (net (code "57") (name "W2_UART5_TXD") (class "Default")
      (node (ref "U731") (pin "G8") (pinfunction "UART_RX_G8") (pintype "passive"))
    )
    (net (code "58") (name "W2_WL_RST") (class "Default")
      (node (ref "U731") (pin "H7") (pinfunction "WL_RST_H7") (pintype "passive"))
    )
    (net (code "59") (name "W2_nDIS1") (class "Default")
      (node (ref "U745") (pin "2") (pinfunction "A1_2") (pintype "bidirectional"))
    )
    (net (code "60") (name "WL_WAKE_HOST") (class "Default")
      (node (ref "U731") (pin "F7") (pinfunction "WL_WAKE_HOST_F7") (pintype "passive"))
    )
    (net (code "61") (name "unconnected-(U731-NC1-PadF1)") (class "Default")
      (node (ref "U731") (pin "F1") (pinfunction "NC1_F1") (pintype "passive+no_connect"))
    )
    (net (code "62") (name "unconnected-(U731-NC2-PadE1)") (class "Default")
      (node (ref "U731") (pin "E1") (pinfunction "NC2_E1") (pintype "passive+no_connect"))
    )
    (net (code "63") (name "unconnected-(U731-NC3-PadD1)") (class "Default")
      (node (ref "U731") (pin "D1") (pinfunction "NC3_D1") (pintype "passive+no_connect"))
    )
    (net (code "64") (name "unconnected-(U731-NC4-PadC1)") (class "Default")
      (node (ref "U731") (pin "C1") (pinfunction "NC4_C1") (pintype "passive+no_connect"))
    )
    (net (code "65") (name "unconnected-(U731-NC5-PadC4)") (class "Default")
      (node (ref "U731") (pin "C4") (pinfunction "NC5_C4") (pintype "passive+no_connect"))
    )
    (net (code "66") (name "unconnected-(U731-NC6-PadC5)") (class "Default")
      (node (ref "U731") (pin "C5") (pinfunction "NC6_C5") (pintype "passive+no_connect"))
    )
    (net (code "67") (name "unconnected-(U731-NC7-PadD9)") (class "Default")
      (node (ref "U731") (pin "D9") (pinfunction "NC7_D9") (pintype "passive+no_connect"))
    )
    (net (code "68") (name "unconnected-(U731-NC8-PadC9)") (class "Default")
      (node (ref "U731") (pin "C9") (pinfunction "NC8_C9") (pintype "passive+no_connect"))
    )
    (net (code "69") (name "unconnected-(U731-NC9-PadB9)") (class "Default")
      (node (ref "U731") (pin "B9") (pinfunction "NC9_B9") (pintype "passive+no_connect"))
    )
    (net (code "70") (name "unconnected-(U731-NC10-PadG1)") (class "Default")
      (node (ref "U731") (pin "G1") (pinfunction "NC10_G1") (pintype "passive+no_connect"))
    )
    (net (code "71") (name "unconnected-(U731-NC11-PadJ2)") (class "Default")
      (node (ref "U731") (pin "J2") (pinfunction "NC11_J2") (pintype "passive+no_connect"))
    )
    (net (code "72") (name "unconnected-(U731-NC12-PadJ1)") (class "Default")
      (node (ref "U731") (pin "J1") (pinfunction "NC12_J1") (pintype "passive+no_connect"))
    )
    (net (code "73") (name "unconnected-(U731-NC13-PadK5)") (class "Default")
      (node (ref "U731") (pin "K5") (pinfunction "NC13_K5") (pintype "passive+no_connect"))
    )
    (net (code "74") (name "unconnected-(U731-NC14-PadH2)") (class "Default")
      (node (ref "U731") (pin "H2") (pinfunction "NC14_H2") (pintype "passive+no_connect"))
    )
    (net (code "75") (name "unconnected-(U731-NC15-PadH1)") (class "Default")
      (node (ref "U731") (pin "H1") (pinfunction "NC15_H1") (pintype "passive+no_connect"))
    )
    (net (code "76") (name "unconnected-(U731-RF_CNTL0-PadH3)") (class "Default")
      (node (ref "U731") (pin "H3") (pinfunction "RF_CNTL0_H3") (pintype "passive+no_connect"))
    )
    (net (code "77") (name "unconnected-(U731-RF_CNTL2-PadG4)") (class "Default")
      (node (ref "U731") (pin "G4") (pinfunction "RF_CNTL2_G4") (pintype "passive+no_connect"))
    )
    (net (code "78") (name "unconnected-(U731-RF_CNTL3-PadF3)") (class "Default")
      (node (ref "U731") (pin "F3") (pinfunction "RF_CNTL3_F3") (pintype "passive+no_connect"))
    )
    (net (code "79") (name "unconnected-(U731-RF_CNTL4-PadG3)") (class "Default")
      (node (ref "U731") (pin "G3") (pinfunction "RF_CNTL4_G3") (pintype "passive+no_connect"))
    )
    (net (code "80") (name "unconnected-(U731-WCI-2_SIN-PadC6)") (class "Default")
      (node (ref "U731") (pin "C6") (pinfunction "WCI-2_SIN_C6") (pintype "passive+no_connect"))
    )
    (net (code "81") (name "unconnected-(U731-WCI-2_SOUT-PadB6)") (class "Default")
      (node (ref "U731") (pin "B6") (pinfunction "WCI-2_SOUT_B6") (pintype "passive+no_connect"))
    )
    (net (code "82") (name "unconnected-(U745-A3-Pad4)") (class "Default")
      (node (ref "U745") (pin "4") (pinfunction "A3_4") (pintype "bidirectional+no_connect"))
    )
    (net (code "83") (name "unconnected-(U745-YB3-Pad8)") (class "Default")
      (node (ref "U745") (pin "8") (pinfunction "YB3_8") (pintype "bidirectional+no_connect"))
    )
    (net (code "84") (name "unconnected-(U748-P5-Pad8)") (class "Default")
      (node (ref "U748") (pin "8") (pinfunction "P5_8") (pintype "passive+no_connect"))
    )
    (net (code "85") (name "unconnected-(U748-P6-Pad9)") (class "Default")
      (node (ref "U748") (pin "9") (pinfunction "P6_9") (pintype "passive+no_connect"))
    )
    (net (code "86") (name "unconnected-(U748-P7-Pad10)") (class "Default")
      (node (ref "U748") (pin "10") (pinfunction "P7_10") (pintype "passive+no_connect"))
    )
    (net (code "87") (name "unconnected-(U748-~{INT}-Pad11)") (class "Default")
      (node (ref "U748") (pin "11") (pinfunction "~{INT}_11") (pintype "passive+no_connect"))
    )
  )
)
